# SUP_1_2_1_8.net
KiCad netlist of a schematic drawn in Altium Designer
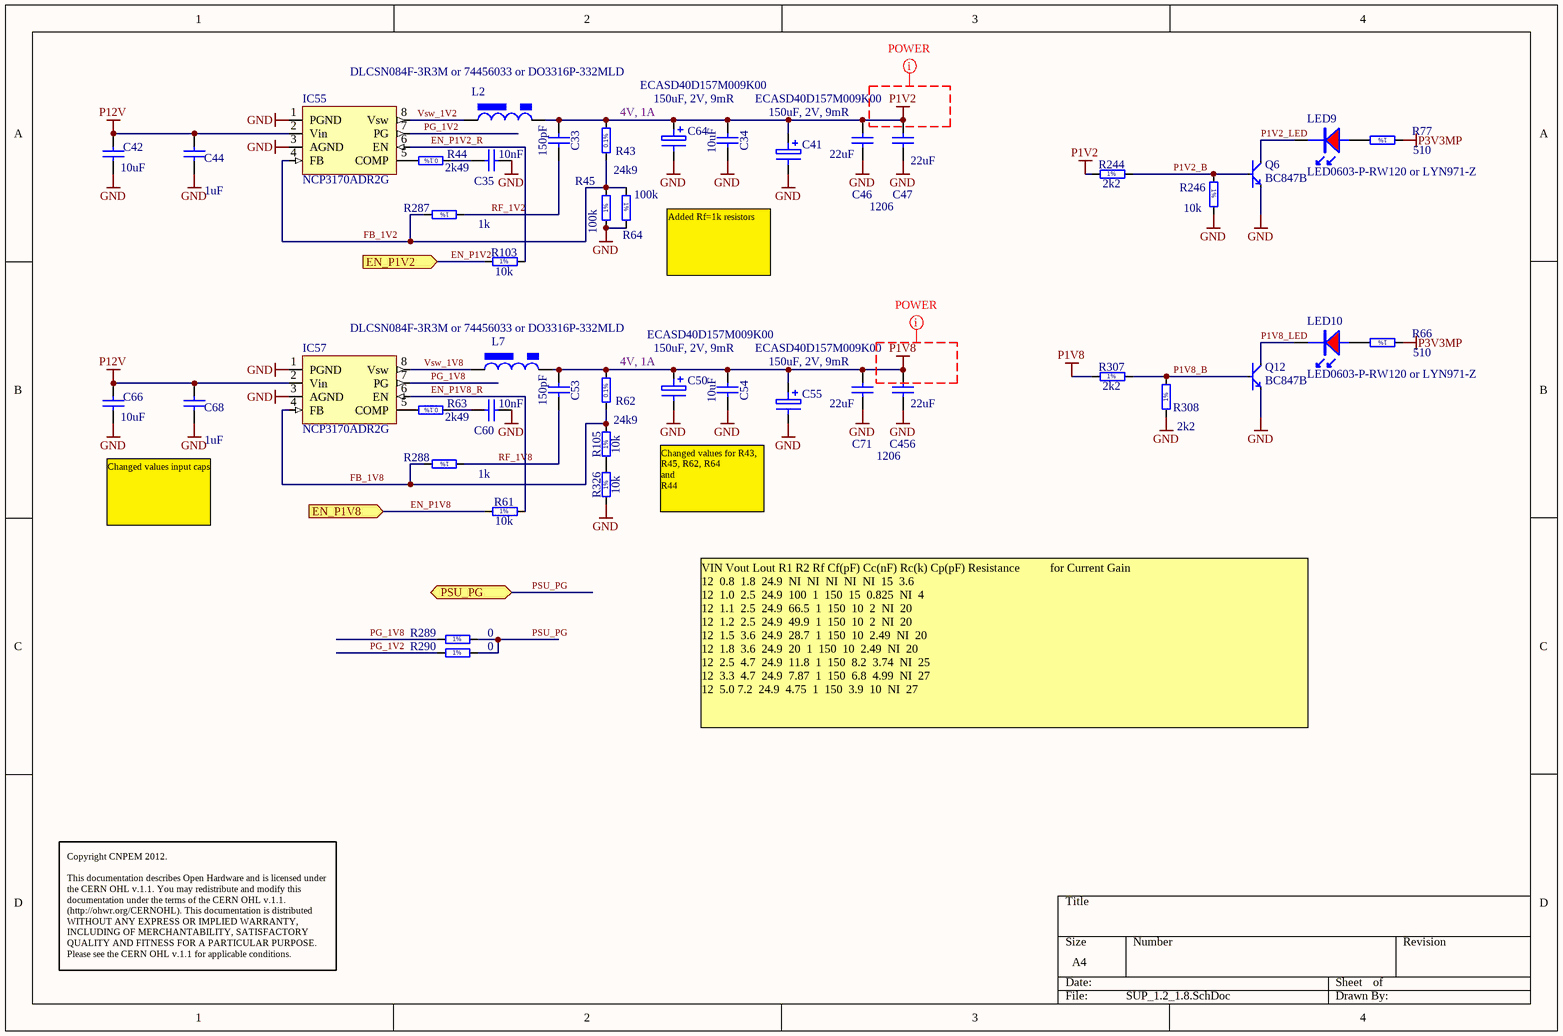
[diagram p0: SUP_1.2_1.8.SchDoc]

(export (version "E")
  (design (tool "Eeschema 10.0.6"))
  (components
    (comp (ref "C33")
      (value "150pF")
      (footprint "CAPC1608X87N")
      (description "Non-polarised capacitor")
      (fields
        (field (name "PART NUMBER") "CC0603_150PF_50V_5%_NP0")
        (field (name "VOLTAGE") "50V")
        (field (name "AUTHOR") "CERN DEM JLC")
      )
      (libsource (lib "Capacitors") (part "Capacitor - non polarized"))
    )
    (comp (ref "C34")
      (value "10uF")
      (footprint "CAPC2012X135N")
      (description "Non-polarised capacitor")
      (fields
        (field (name "PART NUMBER") "CC0805_10UF_16V_10%_X5R")
        (field (name "VOLTAGE") "16V")
        (field (name "AUTHOR") "CERN DEM JLC")
      )
      (libsource (lib "Capacitors") (part "Capacitor - non polarized"))
    )
    (comp (ref "C35")
      (value "10nF")
      (footprint "CAPC1005X55N")
      (description "Non-polarised capacitor")
      (fields
        (field (name "PART NUMBER") "CC0402_10NF_16V_10%_X7R")
        (field (name "VOLTAGE") "16V")
        (field (name "AUTHOR") "CERN DEM JLC")
      )
      (libsource (lib "Capacitors") (part "Capacitor - non polarized"))
    )
    (comp (ref "C41")
      (value "ECASD40D157M009K00")
      (footprint "2917_POLY")
      (description "POLY, 150uF, 2V, ESR: 9mR")
      (fields (field (name "ALTIUM_VALUE") "150uF, 2V, 9mR"))
      (libsource (lib "LIBRARY_SCH") (part "CAP_POLYMER_SMDD"))
    )
    (comp (ref "C42")
      (value "10uF")
      (footprint "CAPC2012X135N")
      (description "Non-polarised capacitor")
      (fields
        (field (name "PART NUMBER") "CC0805_10UF_16V_10%_X5R")
        (field (name "VOLTAGE") "16V")
        (field (name "AUTHOR") "CERN DEM JLC")
      )
      (libsource (lib "Capacitors") (part "Capacitor - non polarized"))
    )
    (comp (ref "C44")
      (value "1uF")
      (footprint "CAPC1608X87N")
      (description "Non-polarised capacitor")
      (fields
        (field (name "PART NUMBER") "CC0603_1UF_16V_10%_X7R")
        (field (name "VOLTAGE") "16V")
        (field (name "AUTHOR") "CERN DEM JLC")
      )
      (libsource (lib "Capacitors") (part "Capacitor - non polarized"))
    )
    (comp (ref "C46")
      (value "22uF")
      (footprint "CAPC3216X180N")
      (description "Non-polarised capacitor")
      (fields
        (field (name "PART NUMBER") "CC1206_22UF_10V_10%_X7R")
        (field (name "VOLTAGE") "10V")
        (field (name "AUTHOR") "CERN DEM JLC")
      )
      (libsource (lib "Capacitors") (part "Capacitor - non polarized"))
    )
    (comp (ref "C47")
      (value "22uF")
      (footprint "CAPC3216X180N")
      (description "Non-polarised capacitor")
      (fields
        (field (name "PART NUMBER") "CC1206_22UF_10V_10%_X7R")
        (field (name "VOLTAGE") "10V")
        (field (name "CASE") "1206")
        (field (name "AUTHOR") "CERN DEM JLC")
      )
      (libsource (lib "Capacitors") (part "Capacitor - non polarized"))
    )
    (comp (ref "C50")
      (value "ECASD40D157M009K00")
      (footprint "2917_POLY")
      (description "POLY, 150uF, 2V, ESR: 9mR")
      (fields (field (name "ALTIUM_VALUE") "150uF, 2V, 9mR"))
      (libsource (lib "LIBRARY_SCH") (part "CAP_POLYMER_SMDD"))
    )
    (comp (ref "C53")
      (value "150pF")
      (footprint "CAPC1608X87N")
      (description "Non-polarised capacitor")
      (fields
        (field (name "PART NUMBER") "CC0603_150PF_50V_5%_NP0")
        (field (name "VOLTAGE") "50V")
        (field (name "AUTHOR") "CERN DEM JLC")
      )
      (libsource (lib "Capacitors") (part "Capacitor - non polarized"))
    )
    (comp (ref "C54")
      (value "10uF")
      (footprint "CAPC2012X135N")
      (description "Non-polarised capacitor")
      (fields
        (field (name "PART NUMBER") "CC0805_10UF_16V_10%_X5R")
        (field (name "VOLTAGE") "16V")
        (field (name "AUTHOR") "CERN DEM JLC")
      )
      (libsource (lib "Capacitors") (part "Capacitor - non polarized"))
    )
    (comp (ref "C55")
      (value "ECASD40D157M009K00")
      (footprint "2917_POLY")
      (description "POLY, 150uF, 2V, ESR: 9mR")
      (fields (field (name "ALTIUM_VALUE") "150uF, 2V, 9mR"))
      (libsource (lib "LIBRARY_SCH") (part "CAP_POLYMER_SMDD"))
    )
    (comp (ref "C60")
      (value "10nF")
      (footprint "CAPC1005X55N")
      (description "Non-polarised capacitor")
      (fields
        (field (name "PART NUMBER") "CC0402_10NF_16V_10%_X7R")
        (field (name "VOLTAGE") "16V")
        (field (name "AUTHOR") "CERN DEM JLC")
      )
      (libsource (lib "Capacitors") (part "Capacitor - non polarized"))
    )
    (comp (ref "C64")
      (value "ECASD40D157M009K00")
      (footprint "2917_POLY")
      (description "POLY, 150uF, 2V, ESR: 9mR")
      (fields (field (name "ALTIUM_VALUE") "150uF, 2V, 9mR"))
      (libsource (lib "LIBRARY_SCH") (part "CAP_POLYMER_SMDD"))
    )
    (comp (ref "C66")
      (value "10uF")
      (footprint "CAPC2012X135N")
      (description "Non-polarised capacitor")
      (fields
        (field (name "PART NUMBER") "CC0805_10UF_16V_10%_X5R")
        (field (name "VOLTAGE") "16V")
        (field (name "AUTHOR") "CERN DEM JLC")
      )
      (libsource (lib "Capacitors") (part "Capacitor - non polarized"))
    )
    (comp (ref "C68")
      (value "1uF")
      (footprint "CAPC1608X87N")
      (description "Non-polarised capacitor")
      (fields
        (field (name "PART NUMBER") "CC0603_1UF_16V_10%_X7R")
        (field (name "VOLTAGE") "16V")
        (field (name "AUTHOR") "CERN DEM JLC")
      )
      (libsource (lib "Capacitors") (part "Capacitor - non polarized"))
    )
    (comp (ref "C71")
      (value "22uF")
      (footprint "CAPC3216X180N")
      (description "Non-polarised capacitor")
      (fields
        (field (name "PART NUMBER") "CC1206_22UF_10V_10%_X7R")
        (field (name "VOLTAGE") "10V")
        (field (name "AUTHOR") "CERN DEM JLC")
      )
      (libsource (lib "Capacitors") (part "Capacitor - non polarized"))
    )
    (comp (ref "C456")
      (value "22uF")
      (footprint "CAPC3216X180N")
      (description "Non-polarised capacitor")
      (fields
        (field (name "PART NUMBER") "CC1206_22UF_10V_10%_X7R")
        (field (name "VOLTAGE") "10V")
        (field (name "CASE") "1206")
        (field (name "AUTHOR") "CERN DEM JLC")
      )
      (libsource (lib "Capacitors") (part "Capacitor - non polarized"))
    )
    (comp (ref "IC55")
      (value "NCP3170ADR2G")
      (footprint "so-8")
      (description "4.5V to 18V, 3A synch buck")
      (libsource (lib "LIBRARY_SCH") (part "PWM_NCP3170"))
    )
    (comp (ref "IC57")
      (value "NCP3170ADR2G")
      (footprint "so-8")
      (description "4.5V to 18V, 3A synch buck")
      (libsource (lib "LIBRARY_SCH") (part "PWM_NCP3170"))
    )
    (comp (ref "L2")
      (value "DLCSN084F-3R3M or 74456033 or DO3316P-332MLD")
      (footprint "IND_CSN084F")
      (description "3.3uH, 20%, 5.4A, 0.015R")
      (libsource (lib "LIBRARY_SCH") (part "L_POWER_CSN084F_3R3"))
    )
    (comp (ref "L7")
      (value "DLCSN084F-3R3M or 74456033 or DO3316P-332MLD")
      (footprint "IND_CSN084F")
      (description "3.3uH, 20%, 5.4A, 0.015R")
      (libsource (lib "LIBRARY_SCH") (part "L_POWER_CSN084F_3R3"))
    )
    (comp (ref "LED9")
      (value "LED0603-P-RW120 or LYN971-Z")
      (footprint "led_0603R")
      (description "LED 0603 red")
      (libsource (lib "LIBRARY_SCH") (part "LED_0603R"))
    )
    (comp (ref "LED10")
      (value "LED0603-P-RW120 or LYN971-Z")
      (footprint "led_0603R")
      (description "LED 0603 red")
      (libsource (lib "LIBRARY_SCH") (part "LED_0603R"))
    )
    (comp (ref "Q6")
      (value "BC847B")
      (footprint "SOT-23")
      (description "Transistor")
      (libsource (lib "LIBRARY_SCH") (part "Q_BC847B"))
    )
    (comp (ref "Q12")
      (value "BC847B")
      (footprint "SOT-23")
      (description "Transistor")
      (libsource (lib "LIBRARY_SCH") (part "Q_BC847B"))
    )
    (comp (ref "R43")
      (value "24k9")
      (footprint "RESC1608X55N")
      (description "Resistor - 0.1%")
      (fields
        (field (name "PART NUMBER") "R0603_24K9_0.1%_0.063W_10PPM")
        (field (name "POWER") "0.063W")
        (field (name "AUTHOR") "CERN DEM JLC")
      )
      (libsource (lib "Resistors") (part "Resistor - 0.1%"))
    )
    (comp (ref "R44")
      (value "2k49")
      (footprint "RESC1608X55N")
      (description "Resistor - 0.1%")
      (fields
        (field (name "PART NUMBER") "R0603_2K49_0.1%_0.063W_10PPM")
        (field (name "POWER") "0.063W")
        (field (name "AUTHOR") "CERN DEM JLC")
      )
      (libsource (lib "Resistors") (part "Resistor - 0.1%"))
    )
    (comp (ref "R45")
      (value "100k")
      (footprint "RESC1005X40N")
      (description "Resistor - 1%")
      (fields
        (field (name "PART NUMBER") "R0402_100K_1%_0.0625W_100PPM")
        (field (name "POWER") "0.0625W")
        (field (name "AUTHOR") "CERN DEM JLC")
      )
      (libsource (lib "Resistors") (part "Resistor - 1%"))
    )
    (comp (ref "R61")
      (value "10k")
      (footprint "RESC1005X40N")
      (description "Resistor - 1%")
      (fields
        (field (name "PART NUMBER") "R0402_10K_1%_0.0625W_100PPM")
        (field (name "POWER") "0.0625W")
        (field (name "AUTHOR") "CERN DEM JLC")
      )
      (libsource (lib "Resistors") (part "Resistor - 1%"))
    )
    (comp (ref "R62")
      (value "24k9")
      (footprint "RESC1608X55N")
      (description "Resistor - 0.1%")
      (fields
        (field (name "PART NUMBER") "R0603_24K9_0.1%_0.063W_10PPM")
        (field (name "POWER") "0.063W")
        (field (name "AUTHOR") "CERN DEM JLC")
      )
      (libsource (lib "Resistors") (part "Resistor - 0.1%"))
    )
    (comp (ref "R63")
      (value "2k49")
      (footprint "RESC1608X55N")
      (description "Resistor - 0.1%")
      (fields
        (field (name "PART NUMBER") "R0603_2K49_0.1%_0.063W_10PPM")
        (field (name "POWER") "0.063W")
        (field (name "AUTHOR") "CERN DEM JLC")
      )
      (libsource (lib "Resistors") (part "Resistor - 0.1%"))
    )
    (comp (ref "R64")
      (value "100k")
      (footprint "RESC1005X40N")
      (description "Resistor - 1%")
      (fields
        (field (name "PART NUMBER") "R0402_100K_1%_0.0625W_100PPM")
        (field (name "POWER") "0.0625W")
        (field (name "AUTHOR") "CERN DEM JLC")
      )
      (libsource (lib "Resistors") (part "Resistor - 1%"))
    )
    (comp (ref "R66")
      (value "510")
      (footprint "RESC1005X40N")
      (description "Resistor - 1%")
      (fields
        (field (name "PART NUMBER") "R0402_510R_1%_0.0625W_100PPM")
        (field (name "POWER") "0.0625W")
        (field (name "AUTHOR") "CERN DEM JLC")
      )
      (libsource (lib "Resistors") (part "Resistor - 1%"))
    )
    (comp (ref "R77")
      (value "510")
      (footprint "RESC1005X40N")
      (description "Resistor - 1%")
      (fields
        (field (name "PART NUMBER") "R0402_510R_1%_0.0625W_100PPM")
        (field (name "POWER") "0.0625W")
        (field (name "AUTHOR") "CERN DEM JLC")
      )
      (libsource (lib "Resistors") (part "Resistor - 1%"))
    )
    (comp (ref "R103")
      (value "10k")
      (footprint "RESC1005X40N")
      (description "Resistor - 1%")
      (fields
        (field (name "PART NUMBER") "R0402_10K_1%_0.0625W_100PPM")
        (field (name "POWER") "0.0625W")
        (field (name "AUTHOR") "CERN DEM JLC")
      )
      (libsource (lib "Resistors") (part "Resistor - 1%"))
    )
    (comp (ref "R105")
      (value "10k")
      (footprint "RESC1005X40N")
      (description "Resistor - 1%")
      (fields
        (field (name "PART NUMBER") "R0402_10K_1%_0.0625W_100PPM")
        (field (name "POWER") "0.0625W")
        (field (name "AUTHOR") "CERN DEM JLC")
      )
      (libsource (lib "Resistors") (part "Resistor - 1%"))
    )
    (comp (ref "R244")
      (value "2k2")
      (footprint "RESC1005X40N")
      (description "Resistor - 1%")
      (fields
        (field (name "PART NUMBER") "R0402_2K2_1%_0.0625W_100PPM")
        (field (name "POWER") "0.0625W")
        (field (name "AUTHOR") "CERN DEM JLC")
      )
      (libsource (lib "Resistors") (part "Resistor - 1%"))
    )
    (comp (ref "R246")
      (value "10k")
      (footprint "RESC1005X40N")
      (description "Resistor - 1%")
      (fields
        (field (name "PART NUMBER") "R0402_10K_1%_0.0625W_100PPM")
        (field (name "POWER") "0.0625W")
        (field (name "AUTHOR") "CERN DEM JLC")
      )
      (libsource (lib "Resistors") (part "Resistor - 1%"))
    )
    (comp (ref "R287")
      (value "1k")
      (footprint "RESC1005X40N")
      (description "Resistor - 1%")
      (fields
        (field (name "PART NUMBER") "R0402_1K_1%_0.0625W_100PPM")
        (field (name "POWER") "0.0625W")
        (field (name "AUTHOR") "CERN DEM JLC")
      )
      (libsource (lib "Resistors") (part "Resistor - 1%"))
    )
    (comp (ref "R288")
      (value "1k")
      (footprint "RESC1005X40N")
      (description "Resistor - 1%")
      (fields
        (field (name "PART NUMBER") "R0402_1K_1%_0.0625W_100PPM")
        (field (name "POWER") "0.0625W")
        (field (name "AUTHOR") "CERN DEM JLC")
      )
      (libsource (lib "Resistors") (part "Resistor - 1%"))
    )
    (comp (ref "R289")
      (value "0")
      (footprint "RESC1005X40N")
      (description "Resistor - 1%")
      (fields
        (field (name "PART NUMBER") "R0402_0R_JUMPER")
        (field (name "MANUFACTURER") "GENERIC")
        (field (name "AUTHOR") "CERN DEM JLC")
      )
      (libsource (lib "Resistors") (part "Resistor - 1%"))
    )
    (comp (ref "R290")
      (value "0")
      (footprint "RESC1005X40N")
      (description "Resistor - 1%")
      (fields
        (field (name "PART NUMBER") "R0402_0R_JUMPER")
        (field (name "MANUFACTURER") "GENERIC")
        (field (name "AUTHOR") "CERN DEM JLC")
      )
      (libsource (lib "Resistors") (part "Resistor - 1%"))
    )
    (comp (ref "R307")
      (value "2k2")
      (footprint "RESC1005X40N")
      (description "Resistor - 1%")
      (fields
        (field (name "PART NUMBER") "R0402_2K2_1%_0.0625W_100PPM")
        (field (name "POWER") "0.0625W")
        (field (name "AUTHOR") "CERN DEM JLC")
      )
      (libsource (lib "Resistors") (part "Resistor - 1%"))
    )
    (comp (ref "R308")
      (value "2k2")
      (footprint "RESC1005X40N")
      (description "Resistor - 1%")
      (fields
        (field (name "PART NUMBER") "R0402_2K2_1%_0.0625W_100PPM")
        (field (name "POWER") "0.0625W")
        (field (name "AUTHOR") "CERN DEM JLC")
      )
      (libsource (lib "Resistors") (part "Resistor - 1%"))
    )
    (comp (ref "R326")
      (value "10k")
      (footprint "RESC1005X40N")
      (description "Resistor - 1%")
      (fields
        (field (name "PART NUMBER") "R0402_10K_1%_0.0625W_100PPM")
        (field (name "POWER") "0.0625W")
        (field (name "AUTHOR") "CERN DEM JLC")
      )
      (libsource (lib "Resistors") (part "Resistor - 1%"))
    )
  )
  (nets
    (net (code "1") (name "/EN_P1V2") (class "Default")
      (node (ref "R103") (pin "1") (pinfunction "1_1") (pintype "passive"))
    )
    (net (code "2") (name "/EN_P1V2_R") (class "Default")
      (node (ref "IC55") (pin "6") (pinfunction "EN_6") (pintype "input"))
      (node (ref "R103") (pin "2") (pinfunction "2_2") (pintype "passive"))
    )
    (net (code "3") (name "/EN_P1V8") (class "Default")
      (node (ref "R61") (pin "1") (pinfunction "1_1") (pintype "passive"))
    )
    (net (code "4") (name "/EN_P1V8_R") (class "Default")
      (node (ref "IC57") (pin "6") (pinfunction "EN_6") (pintype "input"))
      (node (ref "R61") (pin "2") (pinfunction "2_2") (pintype "passive"))
    )
    (net (code "5") (name "/FB_1V2") (class "Default")
      (node (ref "IC55") (pin "4") (pinfunction "FB_4") (pintype "input"))
      (node (ref "R287") (pin "2") (pinfunction "2_2") (pintype "passive"))
      (node (ref "R43") (pin "1") (pinfunction "1_1") (pintype "passive"))
      (node (ref "R45") (pin "2") (pinfunction "2_2") (pintype "passive"))
      (node (ref "R64") (pin "1") (pinfunction "1_1") (pintype "passive"))
    )
    (net (code "6") (name "/FB_1V8") (class "Default")
      (node (ref "IC57") (pin "4") (pinfunction "FB_4") (pintype "input"))
      (node (ref "R105") (pin "2") (pinfunction "2_2") (pintype "passive"))
      (node (ref "R288") (pin "2") (pinfunction "2_2") (pintype "passive"))
      (node (ref "R62") (pin "1") (pinfunction "1_1") (pintype "passive"))
    )
    (net (code "7") (name "/P1V2_B") (class "Default")
      (node (ref "Q6") (pin "1") (pinfunction "B_1") (pintype "passive"))
      (node (ref "R244") (pin "2") (pinfunction "2_2") (pintype "passive"))
      (node (ref "R246") (pin "1") (pinfunction "1_1") (pintype "passive"))
    )
    (net (code "8") (name "/P1V2_LED") (class "Default")
      (node (ref "LED9") (pin "K") (pinfunction "K_K") (pintype "passive"))
      (node (ref "Q6") (pin "3") (pinfunction "C_3") (pintype "passive"))
    )
    (net (code "9") (name "/P1V8_B") (class "Default")
      (node (ref "Q12") (pin "1") (pinfunction "B_1") (pintype "passive"))
      (node (ref "R307") (pin "2") (pinfunction "2_2") (pintype "passive"))
      (node (ref "R308") (pin "2") (pinfunction "2_2") (pintype "passive"))
    )
    (net (code "10") (name "/P1V8_LED") (class "Default")
      (node (ref "LED10") (pin "K") (pinfunction "K_K") (pintype "passive"))
      (node (ref "Q12") (pin "3") (pinfunction "C_3") (pintype "passive"))
    )
    (net (code "11") (name "/PG_1V2") (class "Default")
      (node (ref "IC55") (pin "7") (pinfunction "PG_7") (pintype "output"))
      (node (ref "R290") (pin "2") (pinfunction "2_2") (pintype "passive"))
    )
    (net (code "12") (name "/PG_1V8") (class "Default")
      (node (ref "IC57") (pin "7") (pinfunction "PG_7") (pintype "output"))
      (node (ref "R289") (pin "2") (pinfunction "2_2") (pintype "passive"))
    )
    (net (code "13") (name "/PSU_PG") (class "Default")
      (node (ref "R289") (pin "1") (pinfunction "1_1") (pintype "passive"))
      (node (ref "R290") (pin "1") (pinfunction "1_1") (pintype "passive"))
    )
    (net (code "14") (name "/RF_1V2") (class "Default")
      (node (ref "C33") (pin "2") (pinfunction "2_2") (pintype "passive"))
      (node (ref "R287") (pin "1") (pinfunction "1_1") (pintype "passive"))
    )
    (net (code "15") (name "/RF_1V8") (class "Default")
      (node (ref "C53") (pin "2") (pinfunction "2_2") (pintype "passive"))
      (node (ref "R288") (pin "1") (pinfunction "1_1") (pintype "passive"))
    )
    (net (code "16") (name "/Vsw_1V2") (class "Default")
      (node (ref "IC55") (pin "8") (pinfunction "Vsw_8") (pintype "output"))
      (node (ref "L2") (pin "1") (pintype "passive"))
    )
    (net (code "17") (name "/Vsw_1V8") (class "Default")
      (node (ref "IC57") (pin "8") (pinfunction "Vsw_8") (pintype "output"))
      (node (ref "L7") (pin "1") (pintype "passive"))
    )
    (net (code "18") (name "GND") (class "Default")
      (node (ref "C34") (pin "2") (pinfunction "2_2") (pintype "passive"))
      (node (ref "C35") (pin "2") (pinfunction "2_2") (pintype "passive"))
      (node (ref "C41") (pin "2") (pinfunction "2_2") (pintype "passive"))
      (node (ref "C42") (pin "1") (pinfunction "1_1") (pintype "passive"))
      (node (ref "C44") (pin "1") (pinfunction "1_1") (pintype "passive"))
      (node (ref "C456") (pin "2") (pinfunction "2_2") (pintype "passive"))
      (node (ref "C46") (pin "2") (pinfunction "2_2") (pintype "passive"))
      (node (ref "C47") (pin "2") (pinfunction "2_2") (pintype "passive"))
      (node (ref "C50") (pin "2") (pinfunction "2_2") (pintype "passive"))
      (node (ref "C54") (pin "2") (pinfunction "2_2") (pintype "passive"))
      (node (ref "C55") (pin "2") (pinfunction "2_2") (pintype "passive"))
      (node (ref "C60") (pin "2") (pinfunction "2_2") (pintype "passive"))
      (node (ref "C64") (pin "2") (pinfunction "2_2") (pintype "passive"))
      (node (ref "C66") (pin "1") (pinfunction "1_1") (pintype "passive"))
      (node (ref "C68") (pin "1") (pinfunction "1_1") (pintype "passive"))
      (node (ref "C71") (pin "2") (pinfunction "2_2") (pintype "passive"))
      (node (ref "IC55") (pin "1") (pinfunction "PGND_1") (pintype "power_in"))
      (node (ref "IC55") (pin "3") (pinfunction "AGND_3") (pintype "power_in"))
      (node (ref "IC57") (pin "1") (pinfunction "PGND_1") (pintype "power_in"))
      (node (ref "IC57") (pin "3") (pinfunction "AGND_3") (pintype "power_in"))
      (node (ref "Q12") (pin "2") (pinfunction "E_2") (pintype "passive"))
      (node (ref "Q6") (pin "2") (pinfunction "E_2") (pintype "passive"))
      (node (ref "R246") (pin "2") (pinfunction "2_2") (pintype "passive"))
      (node (ref "R308") (pin "1") (pinfunction "1_1") (pintype "passive"))
      (node (ref "R326") (pin "1") (pinfunction "1_1") (pintype "passive"))
      (node (ref "R45") (pin "1") (pinfunction "1_1") (pintype "passive"))
      (node (ref "R64") (pin "2") (pinfunction "2_2") (pintype "passive"))
    )
    (net (code "19") (name "Net-(C35-Pad1)") (class "Default")
      (node (ref "C35") (pin "1") (pinfunction "1_1") (pintype "passive"))
      (node (ref "R44") (pin "1") (pinfunction "1_1") (pintype "passive"))
    )
    (net (code "20") (name "Net-(C60-Pad1)") (class "Default")
      (node (ref "C60") (pin "1") (pinfunction "1_1") (pintype "passive"))
      (node (ref "R63") (pin "1") (pinfunction "1_1") (pintype "passive"))
    )
    (net (code "21") (name "Net-(IC55-COMP)") (class "Default")
      (node (ref "IC55") (pin "5") (pinfunction "COMP_5") (pintype "passive"))
      (node (ref "R44") (pin "2") (pinfunction "2_2") (pintype "passive"))
    )
    (net (code "22") (name "Net-(IC57-COMP)") (class "Default")
      (node (ref "IC57") (pin "5") (pinfunction "COMP_5") (pintype "passive"))
      (node (ref "R63") (pin "2") (pinfunction "2_2") (pintype "passive"))
    )
    (net (code "23") (name "Net-(LED9-PadA)") (class "Default")
      (node (ref "LED9") (pin "A") (pinfunction "A_A") (pintype "passive"))
      (node (ref "R77") (pin "2") (pinfunction "2_2") (pintype "passive"))
    )
    (net (code "24") (name "Net-(LED10-PadA)") (class "Default")
      (node (ref "LED10") (pin "A") (pinfunction "A_A") (pintype "passive"))
      (node (ref "R66") (pin "2") (pinfunction "2_2") (pintype "passive"))
    )
    (net (code "25") (name "Net-(R105-Pad1)") (class "Default")
      (node (ref "R105") (pin "1") (pinfunction "1_1") (pintype "passive"))
      (node (ref "R326") (pin "2") (pinfunction "2_2") (pintype "passive"))
    )
    (net (code "26") (name "P1V2") (class "Default")
      (node (ref "C33") (pin "1") (pinfunction "1_1") (pintype "passive"))
      (node (ref "C34") (pin "1") (pinfunction "1_1") (pintype "passive"))
      (node (ref "C41") (pin "1") (pinfunction "1_1") (pintype "passive"))
      (node (ref "C46") (pin "1") (pinfunction "1_1") (pintype "passive"))
      (node (ref "C47") (pin "1") (pinfunction "1_1") (pintype "passive"))
      (node (ref "C64") (pin "1") (pinfunction "1_1") (pintype "passive"))
      (node (ref "L2") (pin "2") (pintype "passive"))
      (node (ref "R244") (pin "1") (pinfunction "1_1") (pintype "passive"))
      (node (ref "R43") (pin "2") (pinfunction "2_2") (pintype "passive"))
    )
    (net (code "27") (name "P1V8") (class "Default")
      (node (ref "C456") (pin "1") (pinfunction "1_1") (pintype "passive"))
      (node (ref "C50") (pin "1") (pinfunction "1_1") (pintype "passive"))
      (node (ref "C53") (pin "1") (pinfunction "1_1") (pintype "passive"))
      (node (ref "C54") (pin "1") (pinfunction "1_1") (pintype "passive"))
      (node (ref "C55") (pin "1") (pinfunction "1_1") (pintype "passive"))
      (node (ref "C71") (pin "1") (pinfunction "1_1") (pintype "passive"))
      (node (ref "L7") (pin "2") (pintype "passive"))
      (node (ref "R307") (pin "1") (pinfunction "1_1") (pintype "passive"))
      (node (ref "R62") (pin "2") (pinfunction "2_2") (pintype "passive"))
    )
    (net (code "28") (name "P3V3MP") (class "Default")
      (node (ref "R66") (pin "1") (pinfunction "1_1") (pintype "passive"))
      (node (ref "R77") (pin "1") (pinfunction "1_1") (pintype "passive"))
    )
    (net (code "29") (name "P12V") (class "Default")
      (node (ref "C42") (pin "2") (pinfunction "2_2") (pintype "passive"))
      (node (ref "C44") (pin "2") (pinfunction "2_2") (pintype "passive"))
      (node (ref "C66") (pin "2") (pinfunction "2_2") (pintype "passive"))
      (node (ref "C68") (pin "2") (pinfunction "2_2") (pintype "passive"))
      (node (ref "IC55") (pin "2") (pinfunction "Vin_2") (pintype "power_in"))
      (node (ref "IC57") (pin "2") (pinfunction "Vin_2") (pintype "power_in"))
    )
  )
)
